# GNSS_EN_Signal_Control.net
KiCad netlist of a schematic drawn in Altium Designer
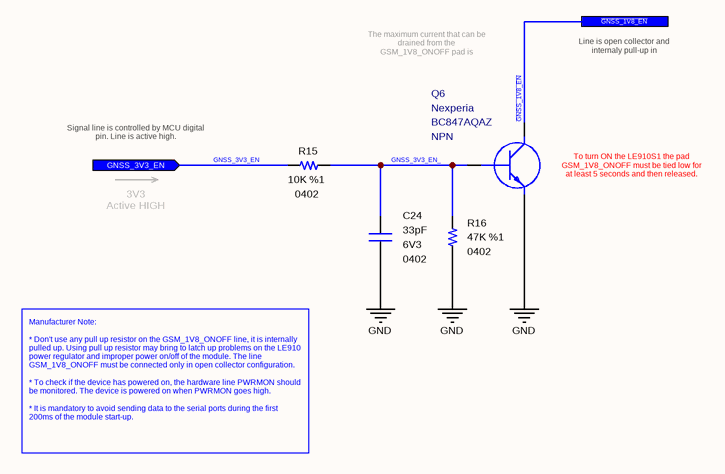
[diagram p0: GNSS EN Signal Control.SchDoc]

(export (version "E")
  (design (tool "Eeschema 10.0.6"))
  (components
    (comp (ref "C24")
      (value "33pF")
      (footprint "CAPACITOR_0402")
      (description "Capacitor - 33pF [0402] (Ceramic)")
      (fields
        (field (name "CASE") "0402")
        (field (name "VOLTAGE") "6V3")
        (field (name "MANUFACTURER PART NUMBER") "C0402C330J9RACAUTO")
        (field (name "TOLERANCE") "10%")
      )
      (libsource (lib "P101DA_Library") (part "33pF [0402-6V3]"))
    )
    (comp (ref "Q6")
      (value "~")
      (footprint "SOT1215")
      (description "Bipolar NPN Transistors")
      (fields
        (field (name "POLARITY") "NPN")
        (field (name "MANUFACTURER PART NUMBER") "BC847AQAZ")
        (field (name "MANUFACTURER NAME") "Nexperia")
      )
      (libsource (lib "P101DA_Library") (part "BC847"))
    )
    (comp (ref "R15")
      (value "10K")
      (footprint "RESISTOR_0402")
      (description "Thick Film Resistors - SMD 1/16 W 10 Kohms 1%")
      (fields
        (field (name "CASE") "0402")
        (field (name "MANUFACTURER PART NUMBER") "CRCW040210K0FKED")
        (field (name "TOLERANCE") "%1")
      )
      (libsource (lib "P101DA_Library") (part "10K"))
    )
    (comp (ref "R16")
      (value "47K")
      (footprint "RESISTOR_0402")
      (description "Thick Film Resistors - SMD 1/16 W 47 Kohms 1%")
      (fields
        (field (name "CASE") "0402")
        (field (name "MANUFACTURER PART NUMBER") "CRCW040247K0FKED")
        (field (name "TOLERANCE") "%1")
      )
      (libsource (lib "P101DA_Library") (part "47K"))
    )
  )
  (nets
    (net (code "1") (name "/GNSS_3V3_EN") (class "Default")
      (node (ref "R15") (pin "2") (pinfunction "2_2") (pintype "passive"))
    )
    (net (code "2") (name "/GNSS_3V3_EN_") (class "Default")
      (node (ref "C24") (pin "2") (pinfunction "2_2") (pintype "passive"))
      (node (ref "Q6") (pin "1") (pinfunction "B_1") (pintype "passive"))
      (node (ref "R15") (pin "1") (pinfunction "1_1") (pintype "passive"))
      (node (ref "R16") (pin "2") (pinfunction "2_2") (pintype "passive"))
    )
    (net (code "3") (name "/~{GNSS_1V8_EN}") (class "Default")
      (node (ref "Q6") (pin "3") (pinfunction "C_3") (pintype "passive"))
    )
    (net (code "4") (name "GND") (class "Default")
      (node (ref "C24") (pin "1") (pinfunction "1_1") (pintype "passive"))
      (node (ref "Q6") (pin "2") (pinfunction "E_2") (pintype "passive"))
      (node (ref "R16") (pin "1") (pinfunction "1_1") (pintype "passive"))
    )
  )
)
